# Volatage_regulator.net
KiCad netlist of a schematic drawn in Altium Designer
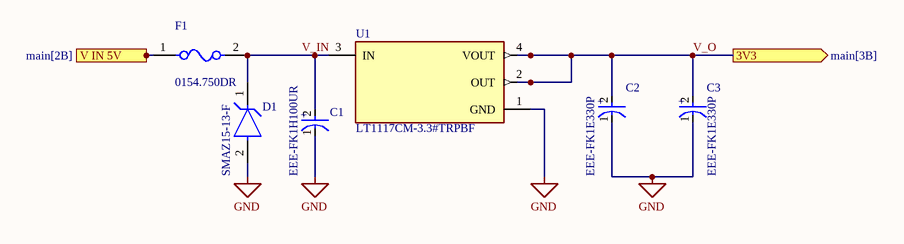
[diagram p0: Volatage_regulator.SchDoc]

(export (version "E")
  (design (tool "Eeschema 10.0.6"))
  (components
    (comp (ref "C1")
      (value "EEE-FK1H100UR")
      (footprint "FP-FKC-MFG")
      (description "CAP ALUM 10UF 20% 50V SMD")
      (fields (field (name "TOLERANCE") "20%") (field (name "VOLTAGE") "50V"))
      (libsource (lib "Altium Content Vault") (part "a00bbbee19879c290e62620ae7e47b1"))
    )
    (comp (ref "C2")
      (value "EEE-FK1E330P")
      (footprint "FP-FKD-MFG")
      (fields (field (name "VOLTAGE") "25V") (field (name "TOLERANCE") "20%"))
      (libsource (lib "Altium Content Vault") (part "cf48714ba7e38822c1575c7ec0b6d1f"))
    )
    (comp (ref "C3")
      (value "EEE-FK1E330P")
      (footprint "FP-FKD-MFG")
      (fields (field (name "VOLTAGE") "25V") (field (name "TOLERANCE") "20%"))
      (libsource (lib "Altium Content Vault") (part "cf48714ba7e38822c1575c7ec0b6d1f"))
    )
    (comp (ref "D1")
      (value "SMAZ15-13-F")
      (footprint "FP-SMA-MFG")
      (description "DIODE ZENER 15V 1W SMA")
      (fields
        (field (name "MANUFACTURER") "Diodes")
        (field (name "OCTOPART") "https://octopart.com/smaz15-13-f-diodes+inc.-334038")
      )
      (libsource (lib "Altium Content Vault") (part "f813f71cba58e380607f5dd3caf9714"))
    )
    (comp (ref "F1")
      (value "0154.750DR")
      (footprint "FP-0154-MFG")
      (description "FUSE BOARD MNT 750MA 125VAC/VDC")
      (fields
        (field (name "MANUFACTURER") "Littelfuse Inc")
        (field (name "OCTOPART") "https://octopart.com/0154.750dr-littelfuse-565855")
      )
      (libsource (lib "Altium Content Vault") (part "5bcf9b9f640e542cf0359d10258e979"))
    )
    (comp (ref "U1")
      (value "LT1117CM-3.3#TRPBF")
      (footprint "FP-M-3-05-08-1460-MFG")
      (description "IC REG LINEAR 3.3V 800MA D2PAK-3")
      (libsource (lib "Altium Content Vault") (part "10d9f824973b5bdfcc5e57233512074"))
    )
  )
  (nets
    (net (code "1") (name "/V IN 5V") (class "Default")
      (node (ref "F1") (pin "1") (pinfunction "1_1") (pintype "passive"))
    )
    (net (code "2") (name "/V_IN") (class "Default")
      (node (ref "C1") (pin "2") (pinfunction "A_2") (pintype "passive"))
      (node (ref "D1") (pin "1") (pinfunction "C_1") (pintype "passive"))
      (node (ref "F1") (pin "2") (pinfunction "2_2") (pintype "passive"))
      (node (ref "U1") (pin "3") (pinfunction "IN_3") (pintype "power_in"))
    )
    (net (code "3") (name "/V_O") (class "Default")
      (node (ref "C2") (pin "2") (pinfunction "A_2") (pintype "passive"))
      (node (ref "C3") (pin "2") (pinfunction "A_2") (pintype "passive"))
      (node (ref "U1") (pin "2") (pinfunction "OUT_2") (pintype "output"))
      (node (ref "U1") (pin "4") (pinfunction "VOUT_4") (pintype "output"))
    )
    (net (code "4") (name "GND") (class "Default")
      (node (ref "C1") (pin "1") (pinfunction "C_1") (pintype "passive"))
      (node (ref "C2") (pin "1") (pinfunction "C_1") (pintype "passive"))
      (node (ref "C3") (pin "1") (pinfunction "C_1") (pintype "passive"))
      (node (ref "D1") (pin "2") (pinfunction "A_2") (pintype "passive"))
      (node (ref "U1") (pin "1") (pinfunction "GND_1") (pintype "power_in"))
    )
  )
)
